# MCU.net
KiCad netlist of a schematic drawn in Altium Designer
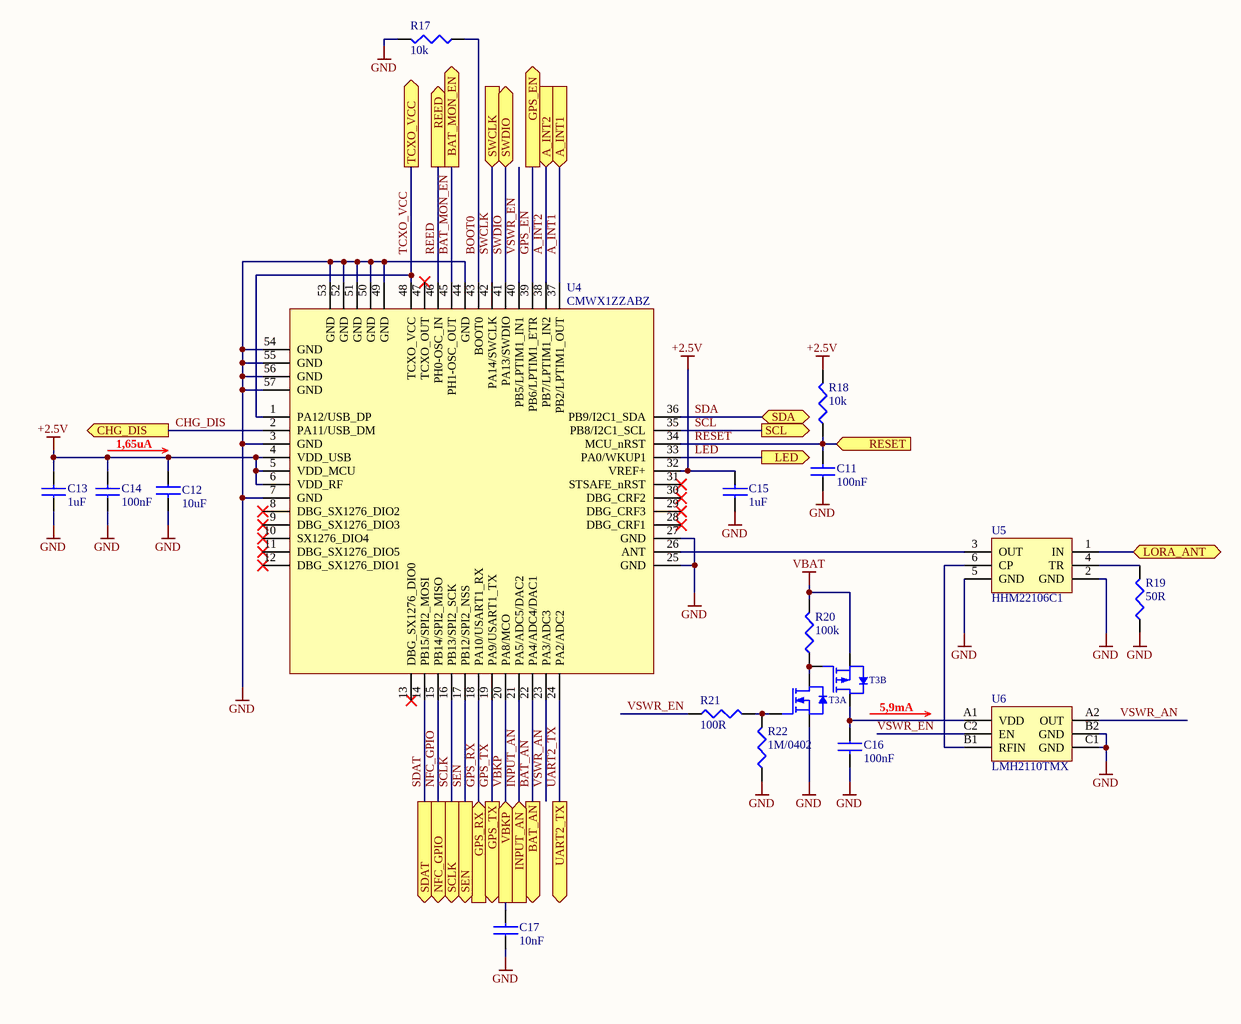
[diagram p0: MCU.SchDoc]

(export (version "E")
  (design (tool "Eeschema 10.0.6"))
  (components
    (comp (ref "C11")
      (value "100nF")
      (footprint "CAP0402")
      (description "0.1 F, 16 V,  5%, X5R, MC Series")
      (fields
        (field (name "MANUFACTURER") "Multicomp")
        (field (name "MANUFACTURER PART NUMBER") "MC0402X104J160CT")
      )
      (libsource (lib "Passive") (part "C - 100nF/0402"))
    )
    (comp (ref "C12")
      (value "10uF")
      (footprint "CAP0603")
      (description "Cap Ceramic 10uF 10V X5R 10% SMD 0603 85C Paper T/R")
      (fields
        (field (name "MANUFACTURER") "Samsung")
        (field (name "MANUFACTURER PART NUMBER") "CL10A106KP8NNNC")
      )
      (libsource (lib "Passive") (part "C - 10uF/10V"))
    )
    (comp (ref "C13")
      (value "1uF")
      (footprint "CAP0402")
      (description "CAP CER 1UF 10V 20% X5R 0402")
      (fields
        (field (name "MANUFACTURER") "Murata")
        (field (name "MANUFACTURER PART NUMBER") "GRM155R61A105ME15D")
      )
      (libsource (lib "Passive") (part "C - 1uF/0402"))
    )
    (comp (ref "C14")
      (value "100nF")
      (footprint "CAP0402")
      (description "0.1 F, 16 V,  5%, X5R, MC Series")
      (fields
        (field (name "MANUFACTURER") "Multicomp")
        (field (name "MANUFACTURER PART NUMBER") "MC0402X104J160CT")
      )
      (libsource (lib "Passive") (part "C - 100nF/0402"))
    )
    (comp (ref "C15")
      (value "1uF")
      (footprint "CAP0402")
      (description "CAP CER 1UF 10V 20% X5R 0402")
      (fields
        (field (name "MANUFACTURER") "Murata")
        (field (name "MANUFACTURER PART NUMBER") "GRM155R61A105ME15D")
      )
      (libsource (lib "Passive") (part "C - 1uF/0402"))
    )
    (comp (ref "C16")
      (value "100nF")
      (footprint "CAP0402")
      (description "0.1 F, 16 V,  5%, X5R, MC Series")
      (fields
        (field (name "MANUFACTURER") "Multicomp")
        (field (name "MANUFACTURER PART NUMBER") "MC0402X104J160CT")
      )
      (libsource (lib "Passive") (part "C - 100nF/0402"))
    )
    (comp (ref "C17")
      (value "10nF")
      (footprint "CAP0402")
      (description "CAP CER 10000PF 16V X7R 0402")
      (fields
        (field (name "MANUFACTURER") "Murata")
        (field (name "MANUFACTURER PART NUMBER") "GRM155R71C103KA01D")
      )
      (libsource (lib "Passive") (part "C - 10nF/0402"))
    )
    (comp (ref "R17")
      (value "10k")
      (footprint "RES0402")
      (description "10 kohm, 50 V, 0402 [1005 Metric], 62.5 mW,  1%, MCWR Series")
      (fields
        (field (name "MANUFACTURER") "Multicomp")
        (field (name "MANUFACTURER PART NUMBER") "MCWR04X1002FTL")
      )
      (libsource (lib "Passive") (part "R - 10k/0402"))
    )
    (comp (ref "R18")
      (value "10k")
      (footprint "RES0402")
      (description "10 kohm, 50 V, 0402 [1005 Metric], 62.5 mW,  1%, MCWR Series")
      (fields
        (field (name "MANUFACTURER") "Multicomp")
        (field (name "MANUFACTURER PART NUMBER") "MCWR04X1002FTL")
      )
      (libsource (lib "Passive") (part "R - 10k/0402"))
    )
    (comp (ref "R19")
      (value "50R")
      (footprint "RES0402")
      (description "50 ohm, FC Series, 30 V, Thin Film, 50 mW")
      (fields
        (field (name "MANUFACTURER") "Vishay")
        (field (name "MANUFACTURER PART NUMBER") "CRCW060351R0FKEA")
      )
      (libsource (lib "Passive") (part "R - 50R"))
    )
    (comp (ref "R20")
      (value "100k")
      (footprint "RES0402")
      (description "100KOHM, 1%, 0.0625W")
      (fields
        (field (name "MANUFACTURER") "Multicomp")
        (field (name "MANUFACTURER PART NUMBER") "MCWR04X1003FTL")
      )
      (libsource (lib "Passive") (part "R - 100k/0402"))
    )
    (comp (ref "R21")
      (value "100R")
      (footprint "RES0402")
      (description "100 ohm, 50 V, 0402 [1005 Metric], 62.5 mW,  1%")
      (fields
        (field (name "MANUFACTURER") "Multicomp")
        (field (name "MANUFACTURER PART NUMBER") "MCMR04X1000FTL")
      )
      (libsource (lib "Passive") (part "R - 100R/0402"))
    )
    (comp (ref "R22")
      (value "1M/0402")
      (footprint "RES0402")
      (description "MCMR04X1004FTL RES, 1M, 1%, 0.0625W, 0402, THICK FILM")
      (fields
        (field (name "MANUFACTURER") "MULTICOMP")
        (field (name "MANUFACTURER PART NUMBER") "MC0063W060311M")
      )
      (libsource (lib "Passive") (part "R - 1M/0402"))
    )
    (comp (ref "T3")
      (value "VT6M1T2CR")
      (footprint "VMT6")
      (description "Dual MOSFET, N and P Channel, 100 mA, 20 V, 2.5 ohm, 4.5 V, 1 V")
      (fields (field (name "AUTHOR") "Ciril Golob"))
      (libsource (lib "Active") (part "T_M - VT6M1T2CR"))
    )
    (comp (ref "U4")
      (value "CMWX1ZZABZ")
      (footprint "Lora Module ES0")
      (description "RF Module, FSK, OOK, LoRa, 4.8Kbps, 915MHz, -135.5dBm, 2.2V to 3.6V, I2C, SPI, UART, USB")
      (fields
        (field (name "MANUFACTURER") "Murata")
        (field (name "MANUFACTURER PART NUMBER") "CMWX1ZZABZ-091")
      )
      (libsource (lib "Active") (part "MCU - CMWX1ZZABZ"))
    )
    (comp (ref "U5")
      (value "HHM22106C1")
      (footprint "HHM22106C1")
      (description "Signal Conditioning DIRECTIONAL COUPLER 700-2700MHz")
      (fields (field (name "MANUFACTURER") "u-blox") (field (name "MANUFACTURER PART NUMBER") "MAX-M8Q-0"))
      (libsource (lib "Active") (part "RF - HHM22106C1"))
    )
    (comp (ref "U6")
      (value "LMH2110TMX")
      (footprint "DSBGA-6")
      (description "RF Detector IC GSM, EDGE, CDMA 50MHz ~ 8GHz -40dBm ~ 5dBm ±0,5dB")
      (fields (field (name "MANUFACTURER") "u-blox") (field (name "MANUFACTURER PART NUMBER") "MAX-M8Q-0"))
      (libsource (lib "Active") (part "RF - LMH2110TMX"))
    )
  )
  (nets
    (net (code "1") (name "+2.5V") (class "Default")
      (node (ref "C12") (pin "1") (pinfunction "1_1") (pintype "passive"))
      (node (ref "C13") (pin "2") (pinfunction "2_2") (pintype "passive"))
      (node (ref "C14") (pin "2") (pinfunction "2_2") (pintype "passive"))
      (node (ref "C15") (pin "2") (pinfunction "2_2") (pintype "passive"))
      (node (ref "R18") (pin "2") (pinfunction "2_2") (pintype "passive"))
      (node (ref "U4") (pin "32") (pinfunction "VREF+_32") (pintype "passive"))
      (node (ref "U4") (pin "4") (pinfunction "VDD_USB_4") (pintype "passive"))
      (node (ref "U4") (pin "5") (pinfunction "VDD_MCU_5") (pintype "passive"))
      (node (ref "U4") (pin "6") (pinfunction "VDD_RF_6") (pintype "passive"))
    )
    (net (code "2") (name "/A_INT1") (class "Default")
      (node (ref "U4") (pin "37") (pinfunction "PB2/LPTIM1_OUT_37") (pintype "passive"))
    )
    (net (code "3") (name "/A_INT2") (class "Default")
      (node (ref "U4") (pin "38") (pinfunction "PB7/LPTIM1_IN2_38") (pintype "passive"))
    )
    (net (code "4") (name "/BAT_AN") (class "Default")
      (node (ref "U4") (pin "22") (pinfunction "PA4/ADC4/DAC1_22") (pintype "passive"))
    )
    (net (code "5") (name "/BAT_MON_EN") (class "Default")
      (node (ref "U4") (pin "45") (pinfunction "PH1-OSC_OUT_45") (pintype "passive"))
    )
    (net (code "6") (name "/BOOT0") (class "Default")
      (node (ref "R17") (pin "1") (pinfunction "1_1") (pintype "passive"))
      (node (ref "U4") (pin "43") (pinfunction "BOOT0_43") (pintype "passive"))
    )
    (net (code "7") (name "/CHG_DIS") (class "Default")
      (node (ref "U4") (pin "2") (pinfunction "PA11/USB_DM_2") (pintype "passive"))
    )
    (net (code "8") (name "/GPS_EN") (class "Default")
      (node (ref "U4") (pin "39") (pinfunction "PB6/LPTIM1_ETR_39") (pintype "passive"))
    )
    (net (code "9") (name "/GPS_RX") (class "Default")
      (node (ref "U4") (pin "18") (pinfunction "PA10/USART1_RX_18") (pintype "passive"))
    )
    (net (code "10") (name "/GPS_TX") (class "Default")
      (node (ref "U4") (pin "19") (pinfunction "PA9/USART1_TX_19") (pintype "passive"))
    )
    (net (code "11") (name "/INPUT_AN") (class "Default")
      (node (ref "U4") (pin "21") (pinfunction "PA5/ADC5/DAC2_21") (pintype "passive"))
    )
    (net (code "12") (name "/LED") (class "Default")
      (node (ref "U4") (pin "33") (pinfunction "PA0/WKUP1_33") (pintype "passive"))
    )
    (net (code "13") (name "/LORA_ANT") (class "Default")
      (node (ref "U5") (pin "1") (pinfunction "IN_1") (pintype "passive"))
    )
    (net (code "14") (name "/NFC_GPIO") (class "Default")
      (node (ref "U4") (pin "15") (pinfunction "PB14/SPI2_MISO_15") (pintype "passive"))
    )
    (net (code "15") (name "/REED") (class "Default")
      (node (ref "U4") (pin "46") (pinfunction "PH0-OSC_IN_46") (pintype "passive"))
    )
    (net (code "16") (name "/RESET") (class "Default")
      (node (ref "C11") (pin "2") (pinfunction "2_2") (pintype "passive"))
      (node (ref "R18") (pin "1") (pinfunction "1_1") (pintype "passive"))
      (node (ref "U4") (pin "34") (pinfunction "MCU_nRST_34") (pintype "passive"))
    )
    (net (code "17") (name "/SCL") (class "Default")
      (node (ref "U4") (pin "35") (pinfunction "PB8/I2C1_SCL_35") (pintype "passive"))
    )
    (net (code "18") (name "/SCLK") (class "Default")
      (node (ref "U4") (pin "16") (pinfunction "PB13/SPI2_SCK_16") (pintype "passive"))
    )
    (net (code "19") (name "/SDA") (class "Default")
      (node (ref "U4") (pin "36") (pinfunction "PB9/I2C1_SDA_36") (pintype "passive"))
    )
    (net (code "20") (name "/SDAT") (class "Default")
      (node (ref "U4") (pin "14") (pinfunction "PB15/SPI2_MOSI_14") (pintype "passive"))
    )
    (net (code "21") (name "/SEN") (class "Default")
      (node (ref "U4") (pin "17") (pinfunction "PB12/SPI2_NSS_17") (pintype "passive"))
    )
    (net (code "22") (name "/SWCLK") (class "Default")
      (node (ref "U4") (pin "42") (pinfunction "PA14/SWCLK_42") (pintype "passive"))
    )
    (net (code "23") (name "/SWDIO") (class "Default")
      (node (ref "U4") (pin "41") (pinfunction "PA13/SWDIO_41") (pintype "passive"))
    )
    (net (code "24") (name "/TCXO_VCC") (class "Default")
      (node (ref "U4") (pin "1") (pinfunction "PA12/USB_DP_1") (pintype "passive"))
      (node (ref "U4") (pin "48") (pinfunction "TCXO_VCC_48") (pintype "passive"))
    )
    (net (code "25") (name "/UART2_TX") (class "Default")
      (node (ref "U4") (pin "24") (pinfunction "PA2/ADC2_24") (pintype "passive"))
    )
    (net (code "26") (name "/VBKP") (class "Default")
      (node (ref "C17") (pin "2") (pinfunction "2_2") (pintype "passive"))
      (node (ref "U4") (pin "20") (pinfunction "PA8/MCO_20") (pintype "passive"))
    )
    (net (code "27") (name "/VSWR_AN") (class "Default")
      (node (ref "U4") (pin "23") (pinfunction "PA3/ADC3_23") (pintype "passive"))
      (node (ref "U6") (pin "A2") (pinfunction "OUT_A2") (pintype "passive"))
    )
    (net (code "28") (name "/VSWR_EN") (class "Default")
      (node (ref "R21") (pin "1") (pinfunction "1_1") (pintype "passive"))
      (node (ref "U4") (pin "40") (pinfunction "PB5/LPTIM1_IN1_40") (pintype "passive"))
      (node (ref "U6") (pin "C2") (pinfunction "EN_C2") (pintype "passive"))
    )
    (net (code "29") (name "GND") (class "Default")
      (node (ref "C11") (pin "1") (pinfunction "1_1") (pintype "passive"))
      (node (ref "C12") (pin "2") (pinfunction "2_2") (pintype "passive"))
      (node (ref "C13") (pin "1") (pinfunction "1_1") (pintype "passive"))
      (node (ref "C14") (pin "1") (pinfunction "1_1") (pintype "passive"))
      (node (ref "C15") (pin "1") (pinfunction "1_1") (pintype "passive"))
      (node (ref "C16") (pin "2") (pinfunction "2_2") (pintype "passive"))
      (node (ref "C17") (pin "1") (pinfunction "1_1") (pintype "passive"))
      (node (ref "R17") (pin "2") (pinfunction "2_2") (pintype "passive"))
      (node (ref "R19") (pin "1") (pinfunction "1_1") (pintype "passive"))
      (node (ref "R22") (pin "1") (pinfunction "1_1") (pintype "passive"))
      (node (ref "T3") (pin "1") (pinfunction "S1_1") (pintype "passive"))
      (node (ref "U4") (pin "25") (pinfunction "GND_25") (pintype "passive"))
      (node (ref "U4") (pin "27") (pinfunction "GND_27") (pintype "passive"))
      (node (ref "U4") (pin "3") (pinfunction "GND_3") (pintype "passive"))
      (node (ref "U4") (pin "44") (pinfunction "GND_44") (pintype "passive"))
      (node (ref "U4") (pin "49") (pinfunction "GND_49") (pintype "passive"))
      (node (ref "U4") (pin "50") (pinfunction "GND_50") (pintype "passive"))
      (node (ref "U4") (pin "51") (pinfunction "GND_51") (pintype "passive"))
      (node (ref "U4") (pin "52") (pinfunction "GND_52") (pintype "passive"))
      (node (ref "U4") (pin "53") (pinfunction "GND_53") (pintype "passive"))
      (node (ref "U4") (pin "54") (pinfunction "GND_54") (pintype "passive"))
      (node (ref "U4") (pin "55") (pinfunction "GND_55") (pintype "passive"))
      (node (ref "U4") (pin "56") (pinfunction "GND_56") (pintype "passive"))
      (node (ref "U4") (pin "57") (pinfunction "GND_57") (pintype "passive"))
      (node (ref "U4") (pin "7") (pinfunction "GND_7") (pintype "passive"))
      (node (ref "U5") (pin "2") (pinfunction "GND_2") (pintype "passive"))
      (node (ref "U5") (pin "5") (pinfunction "GND_5") (pintype "passive"))
      (node (ref "U6") (pin "B2") (pinfunction "GND_B2") (pintype "passive"))
      (node (ref "U6") (pin "C1") (pinfunction "GND_C1") (pintype "passive"))
    )
    (net (code "30") (name "Net-(T3A-D1)") (class "Default")
      (node (ref "R20") (pin "1") (pinfunction "1_1") (pintype "passive"))
      (node (ref "T3") (pin "5") (pinfunction "G2_5") (pintype "passive"))
      (node (ref "T3") (pin "6") (pinfunction "D1_6") (pintype "passive"))
    )
    (net (code "31") (name "Net-(T3A-G1)") (class "Default")
      (node (ref "R21") (pin "2") (pinfunction "2_2") (pintype "passive"))
      (node (ref "R22") (pin "2") (pinfunction "2_2") (pintype "passive"))
      (node (ref "T3") (pin "2") (pinfunction "G1_2") (pintype "passive"))
    )
    (net (code "32") (name "Net-(T3B-D2)") (class "Default")
      (node (ref "C16") (pin "1") (pinfunction "1_1") (pintype "passive"))
      (node (ref "T3") (pin "3") (pinfunction "D2_3") (pintype "passive"))
      (node (ref "U6") (pin "A1") (pinfunction "VDD_A1") (pintype "passive"))
    )
    (net (code "33") (name "Net-(U4-ANT)") (class "Default")
      (node (ref "U4") (pin "26") (pinfunction "ANT_26") (pintype "passive"))
      (node (ref "U5") (pin "3") (pinfunction "OUT_3") (pintype "passive"))
    )
    (net (code "34") (name "Net-(U5-CP)") (class "Default")
      (node (ref "U5") (pin "6") (pinfunction "CP_6") (pintype "passive"))
      (node (ref "U6") (pin "B1") (pinfunction "RFIN_B1") (pintype "passive"))
    )
    (net (code "35") (name "Net-(U5-TR)") (class "Default")
      (node (ref "R19") (pin "2") (pinfunction "2_2") (pintype "passive"))
      (node (ref "U5") (pin "4") (pinfunction "TR_4") (pintype "passive"))
    )
    (net (code "36") (name "VBAT") (class "Default")
      (node (ref "R20") (pin "2") (pinfunction "2_2") (pintype "passive"))
      (node (ref "T3") (pin "4") (pinfunction "S2_4") (pintype "passive"))
    )
    (net (code "37") (name "unconnected-(U4-DBG_CRF1-Pad28)") (class "Default")
      (node (ref "U4") (pin "28") (pinfunction "DBG_CRF1_28") (pintype "passive+no_connect"))
    )
    (net (code "38") (name "unconnected-(U4-DBG_CRF2-Pad30)") (class "Default")
      (node (ref "U4") (pin "30") (pinfunction "DBG_CRF2_30") (pintype "passive+no_connect"))
    )
    (net (code "39") (name "unconnected-(U4-DBG_CRF3-Pad29)") (class "Default")
      (node (ref "U4") (pin "29") (pinfunction "DBG_CRF3_29") (pintype "passive+no_connect"))
    )
    (net (code "40") (name "unconnected-(U4-DBG_SX1276_DIO0-Pad13)") (class "Default")
      (node (ref "U4") (pin "13") (pinfunction "DBG_SX1276_DIO0_13") (pintype "passive+no_connect"))
    )
    (net (code "41") (name "unconnected-(U4-DBG_SX1276_DIO1-Pad12)") (class "Default")
      (node (ref "U4") (pin "12") (pinfunction "DBG_SX1276_DIO1_12") (pintype "passive+no_connect"))
    )
    (net (code "42") (name "unconnected-(U4-DBG_SX1276_DIO2-Pad8)") (class "Default")
      (node (ref "U4") (pin "8") (pinfunction "DBG_SX1276_DIO2_8") (pintype "passive+no_connect"))
    )
    (net (code "43") (name "unconnected-(U4-DBG_SX1276_DIO3-Pad9)") (class "Default")
      (node (ref "U4") (pin "9") (pinfunction "DBG_SX1276_DIO3_9") (pintype "passive+no_connect"))
    )
    (net (code "44") (name "unconnected-(U4-DBG_SX1276_DIO5-Pad11)") (class "Default")
      (node (ref "U4") (pin "11") (pinfunction "DBG_SX1276_DIO5_11") (pintype "passive+no_connect"))
    )
    (net (code "45") (name "unconnected-(U4-STSAFE_nRST-Pad31)") (class "Default")
      (node (ref "U4") (pin "31") (pinfunction "STSAFE_nRST_31") (pintype "passive+no_connect"))
    )
    (net (code "46") (name "unconnected-(U4-SX1276_DIO4-Pad10)") (class "Default")
      (node (ref "U4") (pin "10") (pinfunction "SX1276_DIO4_10") (pintype "passive+no_connect"))
    )
    (net (code "47") (name "unconnected-(U4-TCXO_OUT-Pad47)") (class "Default")
      (node (ref "U4") (pin "47") (pinfunction "TCXO_OUT_47") (pintype "passive+no_connect"))
    )
  )
)
